# Beacon.net
KiCad netlist of a schematic drawn in EAGLE
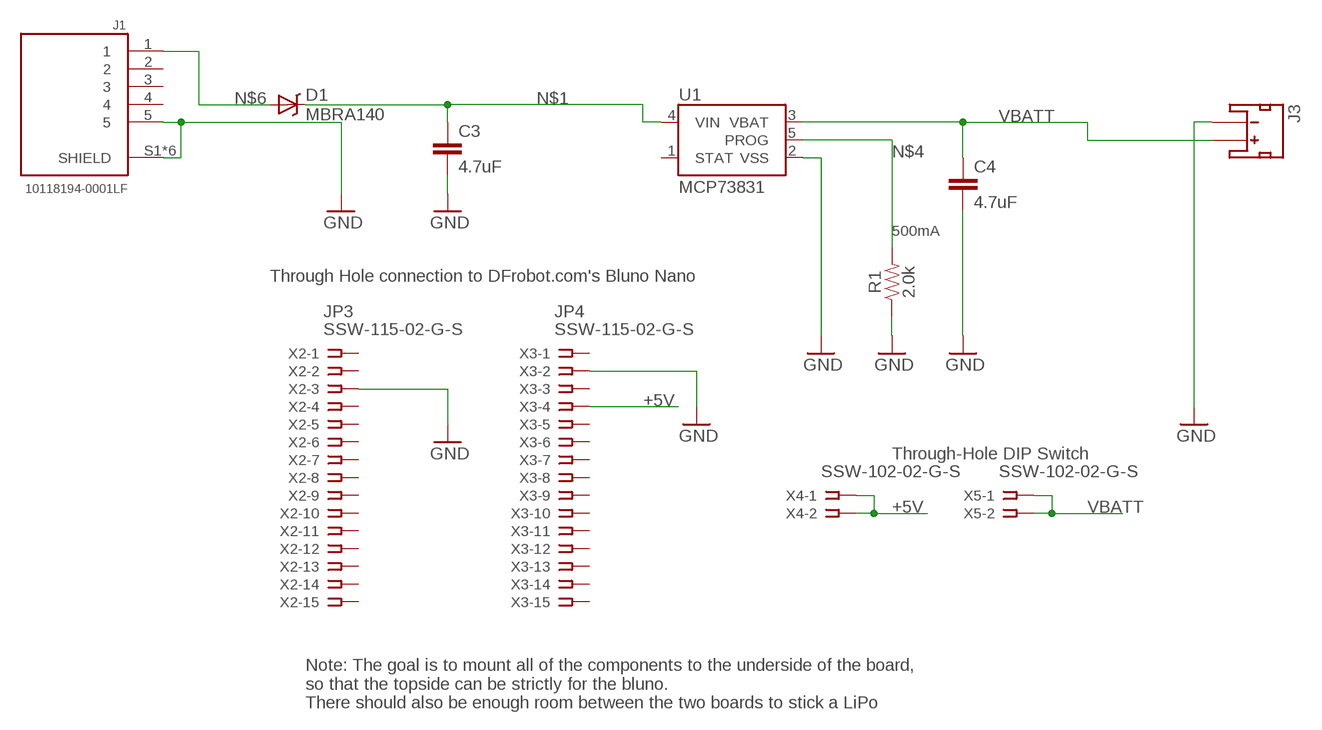
[diagram p0: schematic, sheet 1]

(export (version "E")
  (design (tool "Eeschema 10.0.6"))
  (components
    (comp (ref "C3")
      (value "4.7uF")
      (footprint "eagle-import:0603")
      (libsource (lib "eagle-import") (part "4.7UF0603"))
    )
    (comp (ref "C4")
      (value "4.7uF")
      (footprint "eagle-import:0603")
      (libsource (lib "eagle-import") (part "4.7UF0603"))
    )
    (comp (ref "D1")
      (value "MBRA140")
      (footprint "eagle-import:SMA-DIODE")
      (libsource (lib "eagle-import") (part "MBRA140"))
    )
    (comp (ref "J1")
      (value "10118194-0001LF")
      (footprint "eagle-import:AMPHENOL_10118194-0001LF")
      (fields (field (name "MF") "Amphenol ICC"))
      (libsource (lib "eagle-import") (part "10118194-0001LF"))
    )
    (comp (ref "J3")
      (value "JST_2MM_MALE")
      (footprint "eagle-import:JST-2-SMD")
      (libsource (lib "eagle-import") (part "JST_2MM_MALE"))
    )
    (comp (ref "R1")
      (value "2.0k")
      (footprint "eagle-import:0603")
      (libsource (lib "eagle-import") (part "2.0KOHM-0603-1/10W-5%"))
    )
    (comp (ref "U1")
      (value "MCP73831")
      (footprint "eagle-import:SOT23-5")
      (libsource (lib "eagle-import") (part "MCP73831"))
    )
    (comp (ref "X2")
      (value "SSW-115-02-G-S")
      (footprint "eagle-import:SSW-115-02-G-S")
      (fields (field (name "MF") "Samtec Inc."))
      (libsource (lib "eagle-import") (part "SSW-115-02-G-S"))
    )
    (comp (ref "X3")
      (value "SSW-115-02-G-S")
      (footprint "eagle-import:SSW-115-02-G-S")
      (fields (field (name "MF") "Samtec Inc."))
      (libsource (lib "eagle-import") (part "SSW-115-02-G-S"))
    )
    (comp (ref "X4")
      (value "SSW-102-02-G-S")
      (footprint "eagle-import:SSW-102-02-G-S")
      (fields (field (name "MF") "Samtec Inc."))
      (libsource (lib "eagle-import") (part "SSW-102-02-G-S"))
    )
    (comp (ref "X5")
      (value "SSW-102-02-G-S")
      (footprint "eagle-import:SSW-102-02-G-S")
      (fields (field (name "MF") "Samtec Inc."))
      (libsource (lib "eagle-import") (part "SSW-102-02-G-S"))
    )
  )
  (nets
    (net (code "1") (name "/+5V") (class "Default")
      (node (ref "X3") (pin "4") (pinfunction "1_4") (pintype "passive"))
      (node (ref "X4") (pin "1") (pinfunction "1_1") (pintype "passive"))
      (node (ref "X4") (pin "2") (pinfunction "1_2") (pintype "passive"))
    )
    (net (code "2") (name "/N$1") (class "Default")
      (node (ref "C3") (pin "1") (pinfunction "1_1") (pintype "passive"))
      (node (ref "D1") (pin "C") (pinfunction "C_C") (pintype "passive"))
      (node (ref "U1") (pin "4") (pinfunction "VIN_4") (pintype "power_in"))
    )
    (net (code "3") (name "/N$4") (class "Default")
      (node (ref "R1") (pin "2") (pinfunction "2_2") (pintype "passive"))
      (node (ref "U1") (pin "5") (pinfunction "PROG_5") (pintype "input"))
    )
    (net (code "4") (name "/N$6") (class "Default")
      (node (ref "D1") (pin "A") (pinfunction "A_A") (pintype "passive"))
      (node (ref "J1") (pin "1") (pinfunction "1_1") (pintype "passive"))
    )
    (net (code "5") (name "/VBATT") (class "Default")
      (node (ref "C4") (pin "1") (pinfunction "1_1") (pintype "passive"))
      (node (ref "J3") (pin "2") (pinfunction "+_2") (pintype "bidirectional"))
      (node (ref "U1") (pin "3") (pinfunction "VBAT_3") (pintype "power_in"))
      (node (ref "X5") (pin "1") (pinfunction "1_1") (pintype "passive"))
      (node (ref "X5") (pin "2") (pinfunction "1_2") (pintype "passive"))
    )
    (net (code "6") (name "GND") (class "Default")
      (node (ref "C3") (pin "2") (pinfunction "2_2") (pintype "passive"))
      (node (ref "C4") (pin "2") (pinfunction "2_2") (pintype "passive"))
      (node (ref "J1") (pin "5") (pinfunction "5_5") (pintype "passive"))
      (node (ref "J1") (pin "S1") (pinfunction "SHIELD_S1") (pintype "passive"))
      (node (ref "J1") (pin "S2") (pinfunction "SHIELD_S2") (pintype "passive"))
      (node (ref "J1") (pin "S3") (pinfunction "SHIELD_S3") (pintype "passive"))
      (node (ref "J1") (pin "S4") (pinfunction "SHIELD_S4") (pintype "passive"))
      (node (ref "J1") (pin "S5") (pinfunction "SHIELD_S5") (pintype "passive"))
      (node (ref "J1") (pin "S6") (pinfunction "SHIELD_S6") (pintype "passive"))
      (node (ref "J3") (pin "1") (pinfunction "-_1") (pintype "bidirectional"))
      (node (ref "R1") (pin "1") (pinfunction "1_1") (pintype "passive"))
      (node (ref "U1") (pin "2") (pinfunction "VSS_2") (pintype "power_in"))
      (node (ref "X2") (pin "3") (pinfunction "1_3") (pintype "passive"))
      (node (ref "X3") (pin "2") (pinfunction "1_2") (pintype "passive"))
    )
    (net (code "7") (name "unconnected-(J1-Pad2)") (class "Default")
      (node (ref "J1") (pin "2") (pinfunction "2_2") (pintype "passive"))
    )
    (net (code "8") (name "unconnected-(J1-Pad3)") (class "Default")
      (node (ref "J1") (pin "3") (pinfunction "3_3") (pintype "passive"))
    )
    (net (code "9") (name "unconnected-(J1-Pad4)") (class "Default")
      (node (ref "J1") (pin "4") (pinfunction "4_4") (pintype "passive"))
    )
    (net (code "10") (name "unconnected-(J3-PAD1-PadNC1)") (class "Default")
      (node (ref "J3") (pin "NC1") (pinfunction "PAD1_NC1") (pintype "bidirectional"))
    )
    (net (code "11") (name "unconnected-(J3-PAD2-PadNC2)") (class "Default")
      (node (ref "J3") (pin "NC2") (pinfunction "PAD2_NC2") (pintype "bidirectional"))
    )
    (net (code "12") (name "unconnected-(U1-STAT-Pad1)") (class "Default")
      (node (ref "U1") (pin "1") (pinfunction "STAT_1") (pintype "output"))
    )
    (net (code "13") (name "unconnected-(X2-Pad1)") (class "Default")
      (node (ref "X2") (pin "1") (pinfunction "1_1") (pintype "passive"))
    )
    (net (code "14") (name "unconnected-(X2B-1-Pad10)") (class "Default")
      (node (ref "X2") (pin "10") (pinfunction "1_10") (pintype "passive"))
    )
    (net (code "15") (name "unconnected-(X2C-1-Pad11)") (class "Default")
      (node (ref "X2") (pin "11") (pinfunction "1_11") (pintype "passive"))
    )
    (net (code "16") (name "unconnected-(X2D-1-Pad12)") (class "Default")
      (node (ref "X2") (pin "12") (pinfunction "1_12") (pintype "passive"))
    )
    (net (code "17") (name "unconnected-(X2E-1-Pad13)") (class "Default")
      (node (ref "X2") (pin "13") (pinfunction "1_13") (pintype "passive"))
    )
    (net (code "18") (name "unconnected-(X2F-1-Pad14)") (class "Default")
      (node (ref "X2") (pin "14") (pinfunction "1_14") (pintype "passive"))
    )
    (net (code "19") (name "unconnected-(X2G-1-Pad15)") (class "Default")
      (node (ref "X2") (pin "15") (pinfunction "1_15") (pintype "passive"))
    )
    (net (code "20") (name "unconnected-(X2H-1-Pad2)") (class "Default")
      (node (ref "X2") (pin "2") (pinfunction "1_2") (pintype "passive"))
    )
    (net (code "21") (name "unconnected-(X2J-1-Pad4)") (class "Default")
      (node (ref "X2") (pin "4") (pinfunction "1_4") (pintype "passive"))
    )
    (net (code "22") (name "unconnected-(X2K-1-Pad5)") (class "Default")
      (node (ref "X2") (pin "5") (pinfunction "1_5") (pintype "passive"))
    )
    (net (code "23") (name "unconnected-(X2L-1-Pad6)") (class "Default")
      (node (ref "X2") (pin "6") (pinfunction "1_6") (pintype "passive"))
    )
    (net (code "24") (name "unconnected-(X2M-1-Pad7)") (class "Default")
      (node (ref "X2") (pin "7") (pinfunction "1_7") (pintype "passive"))
    )
    (net (code "25") (name "unconnected-(X2N-1-Pad8)") (class "Default")
      (node (ref "X2") (pin "8") (pinfunction "1_8") (pintype "passive"))
    )
    (net (code "26") (name "unconnected-(X2O-1-Pad9)") (class "Default")
      (node (ref "X2") (pin "9") (pinfunction "1_9") (pintype "passive"))
    )
    (net (code "27") (name "unconnected-(X3-Pad1)") (class "Default")
      (node (ref "X3") (pin "1") (pinfunction "1_1") (pintype "passive"))
    )
    (net (code "28") (name "unconnected-(X3B-1-Pad10)") (class "Default")
      (node (ref "X3") (pin "10") (pinfunction "1_10") (pintype "passive"))
    )
    (net (code "29") (name "unconnected-(X3C-1-Pad11)") (class "Default")
      (node (ref "X3") (pin "11") (pinfunction "1_11") (pintype "passive"))
    )
    (net (code "30") (name "unconnected-(X3D-1-Pad12)") (class "Default")
      (node (ref "X3") (pin "12") (pinfunction "1_12") (pintype "passive"))
    )
    (net (code "31") (name "unconnected-(X3E-1-Pad13)") (class "Default")
      (node (ref "X3") (pin "13") (pinfunction "1_13") (pintype "passive"))
    )
    (net (code "32") (name "unconnected-(X3F-1-Pad14)") (class "Default")
      (node (ref "X3") (pin "14") (pinfunction "1_14") (pintype "passive"))
    )
    (net (code "33") (name "unconnected-(X3G-1-Pad15)") (class "Default")
      (node (ref "X3") (pin "15") (pinfunction "1_15") (pintype "passive"))
    )
    (net (code "34") (name "unconnected-(X3I-1-Pad3)") (class "Default")
      (node (ref "X3") (pin "3") (pinfunction "1_3") (pintype "passive"))
    )
    (net (code "35") (name "unconnected-(X3K-1-Pad5)") (class "Default")
      (node (ref "X3") (pin "5") (pinfunction "1_5") (pintype "passive"))
    )
    (net (code "36") (name "unconnected-(X3L-1-Pad6)") (class "Default")
      (node (ref "X3") (pin "6") (pinfunction "1_6") (pintype "passive"))
    )
    (net (code "37") (name "unconnected-(X3M-1-Pad7)") (class "Default")
      (node (ref "X3") (pin "7") (pinfunction "1_7") (pintype "passive"))
    )
    (net (code "38") (name "unconnected-(X3N-1-Pad8)") (class "Default")
      (node (ref "X3") (pin "8") (pinfunction "1_8") (pintype "passive"))
    )
    (net (code "39") (name "unconnected-(X3O-1-Pad9)") (class "Default")
      (node (ref "X3") (pin "9") (pinfunction "1_9") (pintype "passive"))
    )
  )
)
